# main.net
KiCad netlist of a schematic drawn in Altium Designer
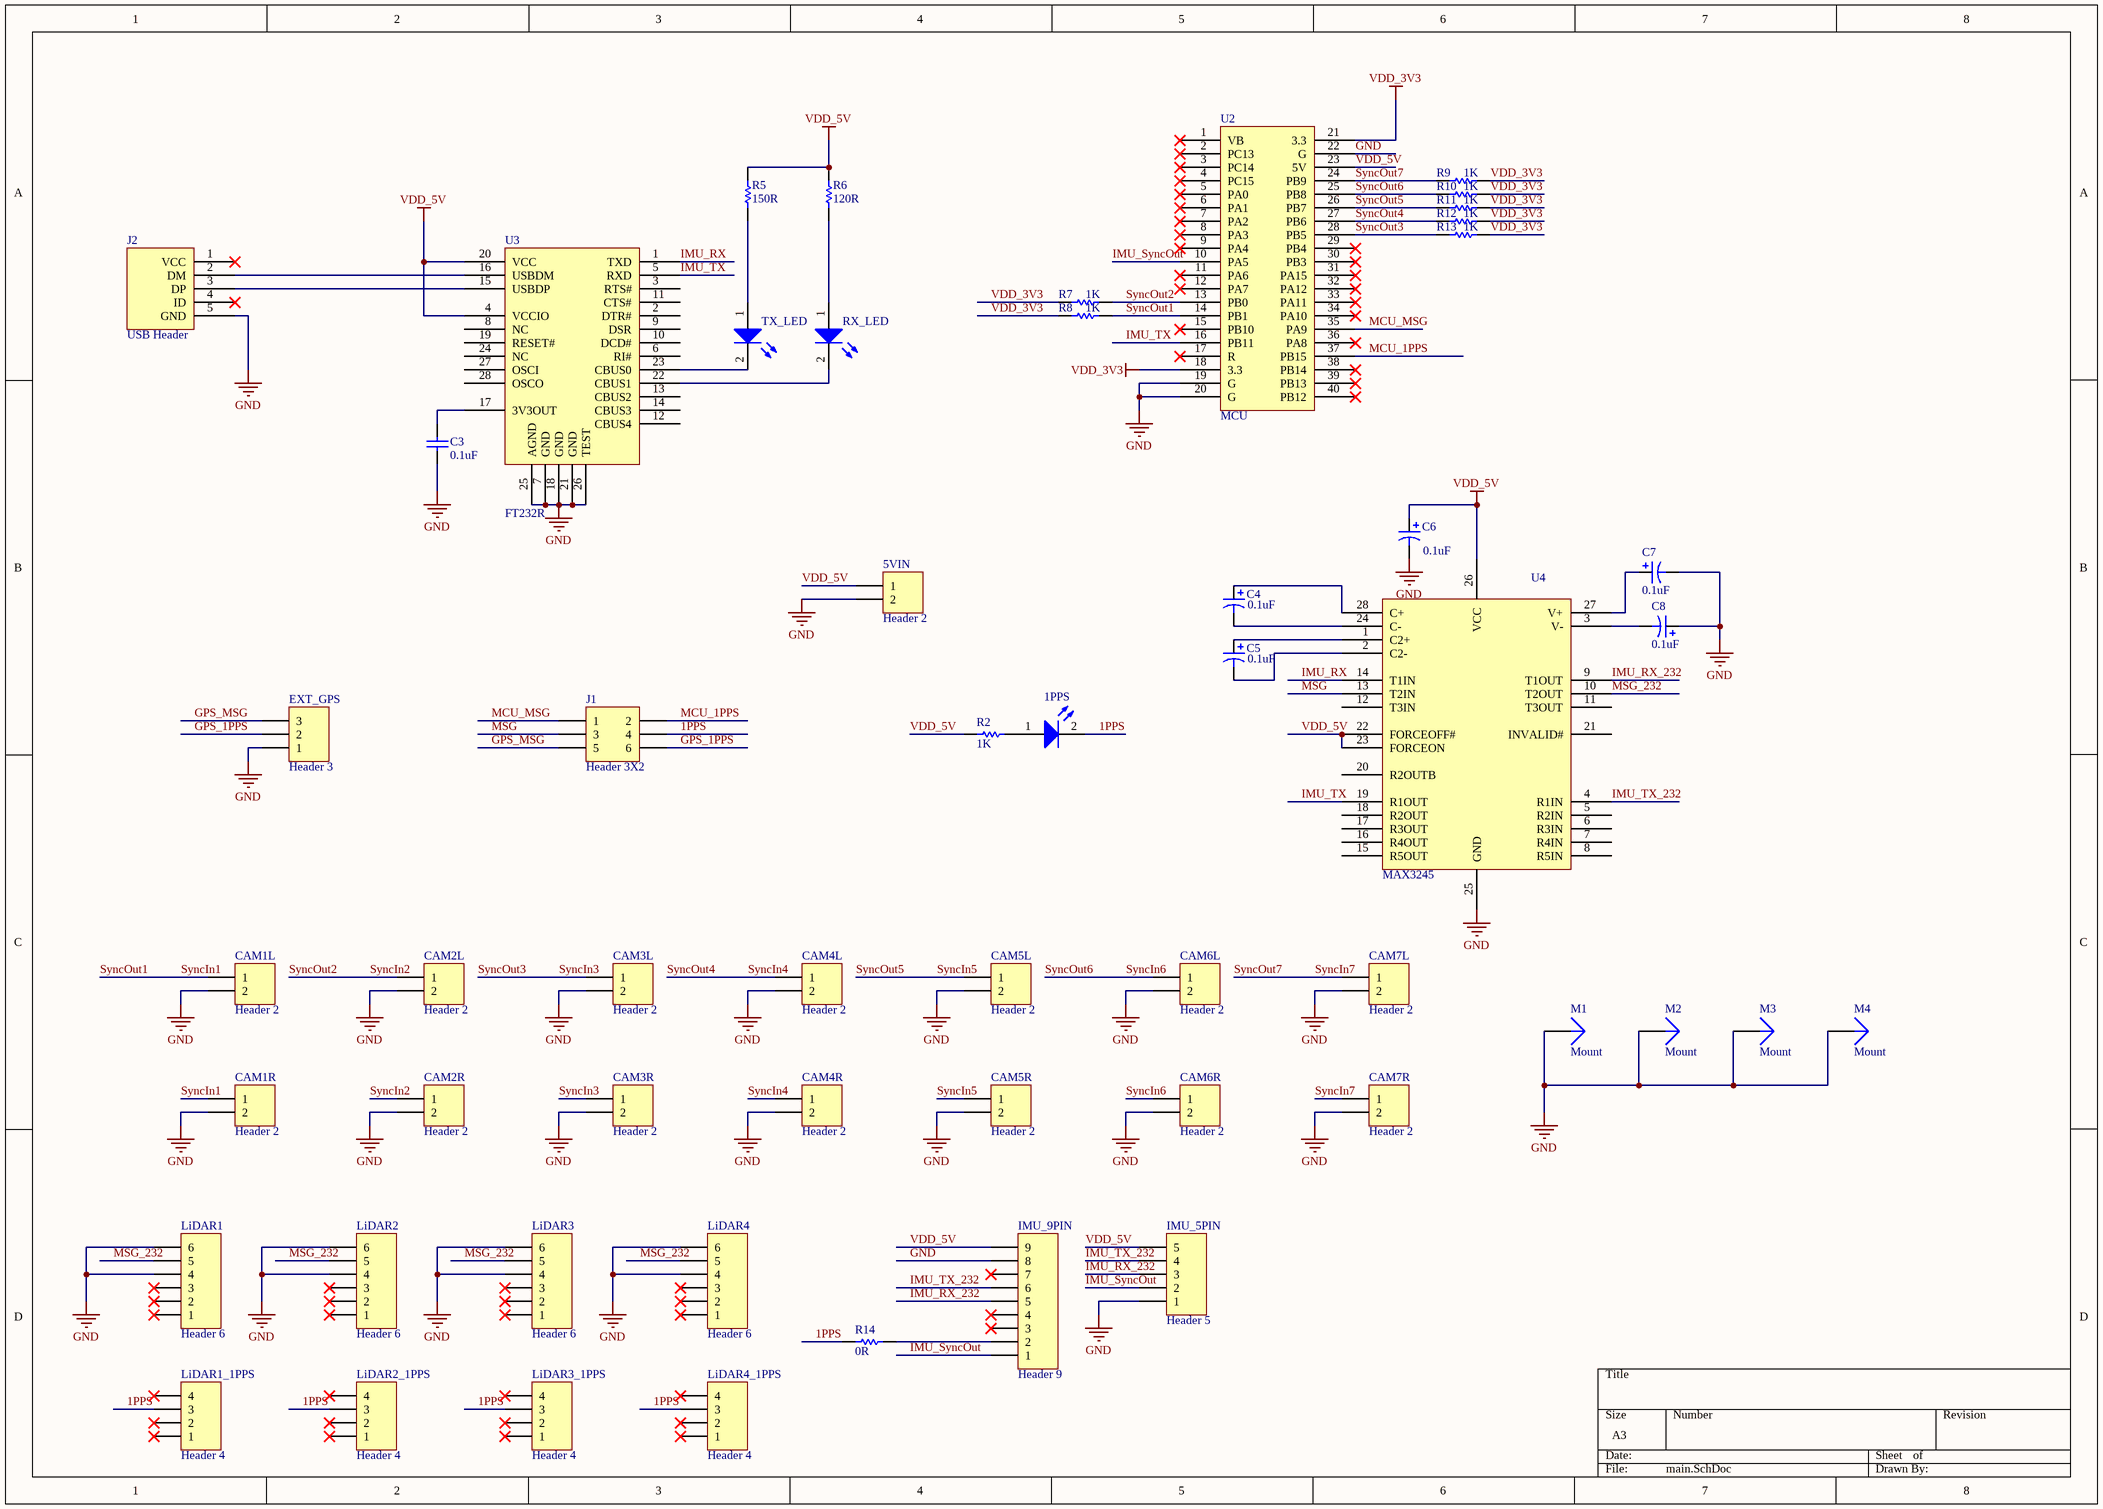
[diagram p0: main.SchDoc]

(export (version "E")
  (design (tool "Eeschema 10.0.6"))
  (components
    (comp (ref "1PPS")
      (value "1PPS LED")
      (footprint "0805D")
      (description "BLUE")
      (fields
        (field (name "MANUFACTURER") "Generic Components")
        (field (name "PUBLISHER") "Altium Hobart Technology Centre")
      )
      (libsource (lib "Miscellaneous Devices") (part "LED2"))
    )
    (comp (ref "5VIN")
      (value "Header 2")
      (footprint "HDR1X2")
      (description "Header, 2-Pin")
      (fields (field (name "PUBLISHER") "Altium Limited"))
      (libsource (lib "Miscellaneous Connectors") (part "Header 2"))
    )
    (comp (ref "C3")
      (value "0.1uF")
      (footprint "0805C")
      (description "Capacitor")
      (fields (field (name "PUBLISHER") "Altium Limited"))
      (libsource (lib "Miscellaneous Devices") (part "Cap"))
    )
    (comp (ref "C4")
      (value "0.1uF")
      (footprint "C1206")
      (description "Polarized Capacitor (Surface Mount)")
      (fields (field (name "PUBLISHER") "Altium Limited"))
      (libsource (lib "Miscellaneous Devices") (part "Cap Pol3"))
    )
    (comp (ref "C5")
      (value "0.1uF")
      (footprint "C1206")
      (description "Polarized Capacitor (Surface Mount)")
      (fields (field (name "PUBLISHER") "Altium Limited"))
      (libsource (lib "Miscellaneous Devices") (part "Cap Pol3"))
    )
    (comp (ref "C6")
      (value "0.1uF")
      (footprint "C1206")
      (description "Polarized Capacitor (Surface Mount)")
      (fields (field (name "PUBLISHER") "Altium Limited"))
      (libsource (lib "Miscellaneous Devices") (part "Cap Pol3"))
    )
    (comp (ref "C7")
      (value "0.1uF")
      (footprint "C1206")
      (description "Polarized Capacitor (Surface Mount)")
      (fields (field (name "PUBLISHER") "Altium Limited"))
      (libsource (lib "Miscellaneous Devices") (part "Cap Pol3"))
    )
    (comp (ref "C8")
      (value "0.1uF")
      (footprint "C1206")
      (description "Polarized Capacitor (Surface Mount)")
      (fields (field (name "PUBLISHER") "Altium Limited"))
      (libsource (lib "Miscellaneous Devices") (part "Cap Pol3"))
    )
    (comp (ref "CAM1L")
      (value "Header 2")
      (footprint "1.25mmP2")
      (description "Header, 2-Pin")
      (fields (field (name "PUBLISHER") "Altium Limited"))
      (libsource (lib "Miscellaneous Connectors") (part "Header 2"))
    )
    (comp (ref "CAM1R")
      (value "Header 2")
      (footprint "1.25mmP2")
      (description "Header, 2-Pin")
      (fields (field (name "PUBLISHER") "Altium Limited"))
      (libsource (lib "Miscellaneous Connectors") (part "Header 2"))
    )
    (comp (ref "CAM2L")
      (value "Header 2")
      (footprint "1.25mmP2")
      (description "Header, 2-Pin")
      (fields (field (name "PUBLISHER") "Altium Limited"))
      (libsource (lib "Miscellaneous Connectors") (part "Header 2"))
    )
    (comp (ref "CAM2R")
      (value "Header 2")
      (footprint "1.25mmP2")
      (description "Header, 2-Pin")
      (fields (field (name "PUBLISHER") "Altium Limited"))
      (libsource (lib "Miscellaneous Connectors") (part "Header 2"))
    )
    (comp (ref "CAM3L")
      (value "Header 2")
      (footprint "1.25mmP2")
      (description "Header, 2-Pin")
      (fields (field (name "PUBLISHER") "Altium Limited"))
      (libsource (lib "Miscellaneous Connectors") (part "Header 2"))
    )
    (comp (ref "CAM3R")
      (value "Header 2")
      (footprint "1.25mmP2")
      (description "Header, 2-Pin")
      (fields (field (name "PUBLISHER") "Altium Limited"))
      (libsource (lib "Miscellaneous Connectors") (part "Header 2"))
    )
    (comp (ref "CAM4L")
      (value "Header 2")
      (footprint "1.25mmP2")
      (description "Header, 2-Pin")
      (fields (field (name "PUBLISHER") "Altium Limited"))
      (libsource (lib "Miscellaneous Connectors") (part "Header 2"))
    )
    (comp (ref "CAM4R")
      (value "Header 2")
      (footprint "1.25mmP2")
      (description "Header, 2-Pin")
      (fields (field (name "PUBLISHER") "Altium Limited"))
      (libsource (lib "Miscellaneous Connectors") (part "Header 2"))
    )
    (comp (ref "CAM5L")
      (value "Header 2")
      (footprint "1.25mmP2")
      (description "Header, 2-Pin")
      (fields (field (name "PUBLISHER") "Altium Limited"))
      (libsource (lib "Miscellaneous Connectors") (part "Header 2"))
    )
    (comp (ref "CAM5R")
      (value "Header 2")
      (footprint "1.25mmP2")
      (description "Header, 2-Pin")
      (fields (field (name "PUBLISHER") "Altium Limited"))
      (libsource (lib "Miscellaneous Connectors") (part "Header 2"))
    )
    (comp (ref "CAM6L")
      (value "Header 2")
      (footprint "1.25mmP2")
      (description "Header, 2-Pin")
      (fields (field (name "PUBLISHER") "Altium Limited"))
      (libsource (lib "Miscellaneous Connectors") (part "Header 2"))
    )
    (comp (ref "CAM6R")
      (value "Header 2")
      (footprint "1.25mmP2")
      (description "Header, 2-Pin")
      (fields (field (name "PUBLISHER") "Altium Limited"))
      (libsource (lib "Miscellaneous Connectors") (part "Header 2"))
    )
    (comp (ref "CAM7L")
      (value "Header 2")
      (footprint "1.25mmP2")
      (description "Header, 2-Pin")
      (fields (field (name "PUBLISHER") "Altium Limited"))
      (libsource (lib "Miscellaneous Connectors") (part "Header 2"))
    )
    (comp (ref "CAM7R")
      (value "Header 2")
      (footprint "1.25mmP2")
      (description "Header, 2-Pin")
      (fields (field (name "PUBLISHER") "Altium Limited"))
      (libsource (lib "Miscellaneous Connectors") (part "Header 2"))
    )
    (comp (ref "EXT_GPS")
      (value "Header 3")
      (footprint "1.25mmP3")
      (description "Header, 3-Pin")
      (fields (field (name "PUBLISHER") "Altium Limited"))
      (libsource (lib "Miscellaneous Connectors") (part "Header 3"))
    )
    (comp (ref "IMU_5PIN")
      (value "Header 5")
      (footprint "1.25mmP5")
      (description "Header, 5-Pin")
      (fields (field (name "PUBLISHER") "Altium Limited"))
      (libsource (lib "Miscellaneous Connectors") (part "Header 5"))
    )
    (comp (ref "IMU_9PIN")
      (value "Header 9")
      (footprint "1.25mmP9")
      (description "Header, 9-Pin")
      (fields (field (name "PUBLISHER") "Altium Limited"))
      (libsource (lib "Miscellaneous Connectors") (part "Header 9"))
    )
    (comp (ref "J1")
      (value "Header 3X2")
      (footprint "HDR2X3")
      (description "Header, 3-Pin, Dual row")
      (fields (field (name "PUBLISHER") "Altium Limited"))
      (libsource (lib "Miscellaneous Connectors") (part "Header 3X2"))
    )
    (comp (ref "J2") (value "USB Header") (footprint "USB2.5-2H4D") (libsource (lib "USB") (part "USB")))
    (comp (ref "LiDAR1")
      (value "Header 6")
      (footprint "1.25mmP6")
      (description "Header, 6-Pin")
      (fields (field (name "PUBLISHER") "Altium Limited"))
      (libsource (lib "Miscellaneous Connectors") (part "Header 6"))
    )
    (comp (ref "LiDAR1_1PPS")
      (value "Header 4")
      (footprint "1.25mmP4")
      (description "Header, 4-Pin")
      (fields (field (name "PUBLISHER") "Altium Limited"))
      (libsource (lib "Miscellaneous Connectors") (part "Header 4"))
    )
    (comp (ref "LiDAR2")
      (value "Header 6")
      (footprint "1.25mmP6")
      (description "Header, 6-Pin")
      (fields (field (name "PUBLISHER") "Altium Limited"))
      (libsource (lib "Miscellaneous Connectors") (part "Header 6"))
    )
    (comp (ref "LiDAR2_1PPS")
      (value "Header 4")
      (footprint "1.25mmP4")
      (description "Header, 4-Pin")
      (fields (field (name "PUBLISHER") "Altium Limited"))
      (libsource (lib "Miscellaneous Connectors") (part "Header 4"))
    )
    (comp (ref "LiDAR3")
      (value "Header 6")
      (footprint "1.25mmP6")
      (description "Header, 6-Pin")
      (fields (field (name "PUBLISHER") "Altium Limited"))
      (libsource (lib "Miscellaneous Connectors") (part "Header 6"))
    )
    (comp (ref "LiDAR3_1PPS")
      (value "Header 4")
      (footprint "1.25mmP4")
      (description "Header, 4-Pin")
      (fields (field (name "PUBLISHER") "Altium Limited"))
      (libsource (lib "Miscellaneous Connectors") (part "Header 4"))
    )
    (comp (ref "LiDAR4")
      (value "Header 6")
      (footprint "1.25mmP6")
      (description "Header, 6-Pin")
      (fields (field (name "PUBLISHER") "Altium Limited"))
      (libsource (lib "Miscellaneous Connectors") (part "Header 6"))
    )
    (comp (ref "LiDAR4_1PPS")
      (value "Header 4")
      (footprint "1.25mmP4")
      (description "Header, 4-Pin")
      (fields (field (name "PUBLISHER") "Altium Limited"))
      (libsource (lib "Miscellaneous Connectors") (part "Header 4"))
    )
    (comp (ref "M1")
      (value "Mount")
      (footprint "安装孔-3.5-5")
      (description "Plug")
      (fields (field (name "PUBLISHER") "Altium Limited"))
      (libsource (lib "Miscellaneous Connectors") (part "Plug"))
    )
    (comp (ref "M2")
      (value "Mount")
      (footprint "安装孔-3.5-5")
      (description "Plug")
      (fields (field (name "PUBLISHER") "Altium Limited"))
      (libsource (lib "Miscellaneous Connectors") (part "Plug"))
    )
    (comp (ref "M3")
      (value "Mount")
      (footprint "安装孔-3.5-5")
      (description "Plug")
      (fields (field (name "PUBLISHER") "Altium Limited"))
      (libsource (lib "Miscellaneous Connectors") (part "Plug"))
    )
    (comp (ref "M4")
      (value "Mount")
      (footprint "安装孔-3.5-5")
      (description "Plug")
      (fields (field (name "PUBLISHER") "Altium Limited"))
      (libsource (lib "Miscellaneous Connectors") (part "Plug"))
    )
    (comp (ref "R2")
      (value "1K")
      (footprint "0805R")
      (description "Resistor")
      (fields
        (field (name "MANUFACTURER") "Generic Components")
        (field (name "PUBLISHER") "Altium Hobart Technology Centre")
      )
      (libsource (lib "HAIBAO_MEGAV1.0_1") (part "Res1"))
    )
    (comp (ref "R5")
      (value "150R")
      (footprint "0805R")
      (description "Resistor")
      (fields
        (field (name "MANUFACTURER") "Generic Components")
        (field (name "PUBLISHER") "Altium Hobart Technology Centre")
      )
      (libsource (lib "HAIBAO_MEGAV1.0_1") (part "Res1"))
    )
    (comp (ref "R6")
      (value "120R")
      (footprint "0805R")
      (description "Resistor")
      (fields
        (field (name "MANUFACTURER") "Generic Components")
        (field (name "PUBLISHER") "Altium Hobart Technology Centre")
      )
      (libsource (lib "HAIBAO_MEGAV1.0_1") (part "Res1"))
    )
    (comp (ref "R7")
      (value "1K")
      (footprint "0805R")
      (description "Resistor")
      (fields
        (field (name "MANUFACTURER") "Generic Components")
        (field (name "PUBLISHER") "Altium Hobart Technology Centre")
      )
      (libsource (lib "HAIBAO_MEGAV1.0_1") (part "Res1"))
    )
    (comp (ref "R8")
      (value "1K")
      (footprint "0805R")
      (description "Resistor")
      (fields
        (field (name "MANUFACTURER") "Generic Components")
        (field (name "PUBLISHER") "Altium Hobart Technology Centre")
      )
      (libsource (lib "HAIBAO_MEGAV1.0_1") (part "Res1"))
    )
    (comp (ref "R9")
      (value "1K")
      (footprint "0805R")
      (description "Resistor")
      (fields
        (field (name "MANUFACTURER") "Generic Components")
        (field (name "PUBLISHER") "Altium Hobart Technology Centre")
      )
      (libsource (lib "HAIBAO_MEGAV1.0_1") (part "Res1"))
    )
    (comp (ref "R10")
      (value "1K")
      (footprint "0805R")
      (description "Resistor")
      (fields
        (field (name "MANUFACTURER") "Generic Components")
        (field (name "PUBLISHER") "Altium Hobart Technology Centre")
      )
      (libsource (lib "HAIBAO_MEGAV1.0_1") (part "Res1"))
    )
    (comp (ref "R11")
      (value "1K")
      (footprint "0805R")
      (description "Resistor")
      (fields
        (field (name "MANUFACTURER") "Generic Components")
        (field (name "PUBLISHER") "Altium Hobart Technology Centre")
      )
      (libsource (lib "HAIBAO_MEGAV1.0_1") (part "Res1"))
    )
    (comp (ref "R12")
      (value "1K")
      (footprint "0805R")
      (description "Resistor")
      (fields
        (field (name "MANUFACTURER") "Generic Components")
        (field (name "PUBLISHER") "Altium Hobart Technology Centre")
      )
      (libsource (lib "HAIBAO_MEGAV1.0_1") (part "Res1"))
    )
    (comp (ref "R13")
      (value "1K")
      (footprint "0805R")
      (description "Resistor")
      (fields
        (field (name "MANUFACTURER") "Generic Components")
        (field (name "PUBLISHER") "Altium Hobart Technology Centre")
      )
      (libsource (lib "HAIBAO_MEGAV1.0_1") (part "Res1"))
    )
    (comp (ref "R14")
      (value "0R")
      (footprint "0805R")
      (description "Resistor")
      (fields
        (field (name "MANUFACTURER") "Generic Components")
        (field (name "PUBLISHER") "Altium Hobart Technology Centre")
      )
      (libsource (lib "HAIBAO_MEGAV1.0_1") (part "Res1"))
    )
    (comp (ref "RX_LED")
      (value "USB RX LED")
      (footprint "0805D")
      (description "GREEN")
      (fields
        (field (name "MANUFACTURER") "Generic Components")
        (field (name "PUBLISHER") "Altium Hobart Technology Centre")
      )
      (libsource (lib "Miscellaneous Devices") (part "LED2"))
    )
    (comp (ref "TX_LED")
      (value "USB TX LED")
      (footprint "0805D")
      (description "YELLOW")
      (fields
        (field (name "MANUFACTURER") "Generic Components")
        (field (name "PUBLISHER") "Altium Hobart Technology Centre")
      )
      (libsource (lib "Miscellaneous Devices") (part "LED2"))
    )
    (comp (ref "U2") (value "MCU") (footprint "STM32Board") (libsource (lib "MCU") (part "MCU")))
    (comp (ref "U3") (value "FT232R") (footprint "SSOP-28") (libsource (lib "FT232R") (part "FT232R")))
    (comp (ref "U4") (value "MAX3245") (footprint "SSOP-28") (libsource (lib "MAX3245") (part "MAX3245")))
  )
  (nets
    (net (code "1") (name "/1PPS") (class "Default")
      (node (ref "1PPS") (pin "2") (pinfunction "K_2") (pintype "passive"))
      (node (ref "J1") (pin "4") (pinfunction "4_4") (pintype "passive"))
      (node (ref "LiDAR1_1PPS") (pin "3") (pinfunction "3_3") (pintype "passive"))
      (node (ref "LiDAR2_1PPS") (pin "3") (pinfunction "3_3") (pintype "passive"))
      (node (ref "LiDAR3_1PPS") (pin "3") (pinfunction "3_3") (pintype "passive"))
      (node (ref "LiDAR4_1PPS") (pin "3") (pinfunction "3_3") (pintype "passive"))
      (node (ref "R14") (pin "1") (pinfunction "1_1") (pintype "passive"))
    )
    (net (code "2") (name "/GPS_1PPS") (class "Default")
      (node (ref "EXT_GPS") (pin "2") (pinfunction "2_2") (pintype "passive"))
      (node (ref "J1") (pin "6") (pinfunction "6_6") (pintype "passive"))
    )
    (net (code "3") (name "/GPS_MSG") (class "Default")
      (node (ref "EXT_GPS") (pin "3") (pinfunction "3_3") (pintype "passive"))
      (node (ref "J1") (pin "5") (pinfunction "5_5") (pintype "passive"))
    )
    (net (code "4") (name "/IMU_RX") (class "Default")
      (node (ref "U3") (pin "1") (pinfunction "TXD_1") (pintype "passive"))
      (node (ref "U4") (pin "14") (pinfunction "T1IN_14") (pintype "passive"))
    )
    (net (code "5") (name "/IMU_RX_232") (class "Default")
      (node (ref "IMU_5PIN") (pin "3") (pinfunction "3_3") (pintype "passive"))
      (node (ref "IMU_9PIN") (pin "5") (pinfunction "5_5") (pintype "passive"))
      (node (ref "U4") (pin "9") (pinfunction "T1OUT_9") (pintype "passive"))
    )
    (net (code "6") (name "/IMU_SyncOut") (class "Default")
      (node (ref "IMU_5PIN") (pin "2") (pinfunction "2_2") (pintype "passive"))
      (node (ref "IMU_9PIN") (pin "1") (pinfunction "1_1") (pintype "passive"))
      (node (ref "U2") (pin "10") (pinfunction "PA5_10") (pintype "passive"))
    )
    (net (code "7") (name "/IMU_TX") (class "Default")
      (node (ref "U2") (pin "16") (pinfunction "PB11_16") (pintype "passive"))
      (node (ref "U3") (pin "5") (pinfunction "RXD_5") (pintype "passive"))
      (node (ref "U4") (pin "19") (pinfunction "R1OUT_19") (pintype "passive"))
    )
    (net (code "8") (name "/IMU_TX_232") (class "Default")
      (node (ref "IMU_5PIN") (pin "4") (pinfunction "4_4") (pintype "passive"))
      (node (ref "IMU_9PIN") (pin "6") (pinfunction "6_6") (pintype "passive"))
      (node (ref "U4") (pin "4") (pinfunction "R1IN_4") (pintype "passive"))
    )
    (net (code "9") (name "/MCU_1PPS") (class "Default")
      (node (ref "J1") (pin "2") (pinfunction "2_2") (pintype "passive"))
      (node (ref "U2") (pin "37") (pinfunction "PB15_37") (pintype "passive"))
    )
    (net (code "10") (name "/MCU_MSG") (class "Default")
      (node (ref "J1") (pin "1") (pinfunction "1_1") (pintype "passive"))
      (node (ref "U2") (pin "35") (pinfunction "PA9_35") (pintype "passive"))
    )
    (net (code "11") (name "/MSG") (class "Default")
      (node (ref "J1") (pin "3") (pinfunction "3_3") (pintype "passive"))
      (node (ref "U4") (pin "13") (pinfunction "T2IN_13") (pintype "passive"))
    )
    (net (code "12") (name "/MSG_232") (class "Default")
      (node (ref "LiDAR1") (pin "5") (pinfunction "5_5") (pintype "passive"))
      (node (ref "LiDAR2") (pin "5") (pinfunction "5_5") (pintype "passive"))
      (node (ref "LiDAR3") (pin "5") (pinfunction "5_5") (pintype "passive"))
      (node (ref "LiDAR4") (pin "5") (pinfunction "5_5") (pintype "passive"))
      (node (ref "U4") (pin "10") (pinfunction "T2OUT_10") (pintype "passive"))
    )
    (net (code "13") (name "/SyncIn1") (class "Default")
      (node (ref "CAM1L") (pin "1") (pinfunction "1_1") (pintype "passive"))
      (node (ref "CAM1R") (pin "1") (pinfunction "1_1") (pintype "passive"))
      (node (ref "R8") (pin "1") (pinfunction "1_1") (pintype "passive"))
      (node (ref "U2") (pin "14") (pinfunction "PB1_14") (pintype "passive"))
    )
    (net (code "14") (name "/SyncIn2") (class "Default")
      (node (ref "CAM2L") (pin "1") (pinfunction "1_1") (pintype "passive"))
      (node (ref "CAM2R") (pin "1") (pinfunction "1_1") (pintype "passive"))
      (node (ref "R7") (pin "1") (pinfunction "1_1") (pintype "passive"))
      (node (ref "U2") (pin "13") (pinfunction "PB0_13") (pintype "passive"))
    )
    (net (code "15") (name "/SyncIn3") (class "Default")
      (node (ref "CAM3L") (pin "1") (pinfunction "1_1") (pintype "passive"))
      (node (ref "CAM3R") (pin "1") (pinfunction "1_1") (pintype "passive"))
      (node (ref "R13") (pin "2") (pinfunction "2_2") (pintype "passive"))
      (node (ref "U2") (pin "28") (pinfunction "PB5_28") (pintype "passive"))
    )
    (net (code "16") (name "/SyncIn4") (class "Default")
      (node (ref "CAM4L") (pin "1") (pinfunction "1_1") (pintype "passive"))
      (node (ref "CAM4R") (pin "1") (pinfunction "1_1") (pintype "passive"))
      (node (ref "R12") (pin "2") (pinfunction "2_2") (pintype "passive"))
      (node (ref "U2") (pin "27") (pinfunction "PB6_27") (pintype "passive"))
    )
    (net (code "17") (name "/SyncIn5") (class "Default")
      (node (ref "CAM5L") (pin "1") (pinfunction "1_1") (pintype "passive"))
      (node (ref "CAM5R") (pin "1") (pinfunction "1_1") (pintype "passive"))
      (node (ref "R11") (pin "2") (pinfunction "2_2") (pintype "passive"))
      (node (ref "U2") (pin "26") (pinfunction "PB7_26") (pintype "passive"))
    )
    (net (code "18") (name "/SyncIn6") (class "Default")
      (node (ref "CAM6L") (pin "1") (pinfunction "1_1") (pintype "passive"))
      (node (ref "CAM6R") (pin "1") (pinfunction "1_1") (pintype "passive"))
      (node (ref "R10") (pin "2") (pinfunction "2_2") (pintype "passive"))
      (node (ref "U2") (pin "25") (pinfunction "PB8_25") (pintype "passive"))
    )
    (net (code "19") (name "/SyncIn7") (class "Default")
      (node (ref "CAM7L") (pin "1") (pinfunction "1_1") (pintype "passive"))
      (node (ref "CAM7R") (pin "1") (pinfunction "1_1") (pintype "passive"))
      (node (ref "R9") (pin "2") (pinfunction "2_2") (pintype "passive"))
      (node (ref "U2") (pin "24") (pinfunction "PB9_24") (pintype "passive"))
    )
    (net (code "20") (name "GND") (class "Default")
      (node (ref "5VIN") (pin "2") (pinfunction "2_2") (pintype "passive"))
      (node (ref "C3") (pin "1") (pinfunction "1_1") (pintype "passive"))
      (node (ref "C6") (pin "2") (pinfunction "2_2") (pintype "passive"))
      (node (ref "C7") (pin "2") (pinfunction "2_2") (pintype "passive"))
      (node (ref "C8") (pin "1") (pinfunction "1_1") (pintype "passive"))
      (node (ref "CAM1L") (pin "2") (pinfunction "2_2") (pintype "passive"))
      (node (ref "CAM1R") (pin "2") (pinfunction "2_2") (pintype "passive"))
      (node (ref "CAM2L") (pin "2") (pinfunction "2_2") (pintype "passive"))
      (node (ref "CAM2R") (pin "2") (pinfunction "2_2") (pintype "passive"))
      (node (ref "CAM3L") (pin "2") (pinfunction "2_2") (pintype "passive"))
      (node (ref "CAM3R") (pin "2") (pinfunction "2_2") (pintype "passive"))
      (node (ref "CAM4L") (pin "2") (pinfunction "2_2") (pintype "passive"))
      (node (ref "CAM4R") (pin "2") (pinfunction "2_2") (pintype "passive"))
      (node (ref "CAM5L") (pin "2") (pinfunction "2_2") (pintype "passive"))
      (node (ref "CAM5R") (pin "2") (pinfunction "2_2") (pintype "passive"))
      (node (ref "CAM6L") (pin "2") (pinfunction "2_2") (pintype "passive"))
      (node (ref "CAM6R") (pin "2") (pinfunction "2_2") (pintype "passive"))
      (node (ref "CAM7L") (pin "2") (pinfunction "2_2") (pintype "passive"))
      (node (ref "CAM7R") (pin "2") (pinfunction "2_2") (pintype "passive"))
      (node (ref "EXT_GPS") (pin "1") (pinfunction "1_1") (pintype "passive"))
      (node (ref "IMU_5PIN") (pin "1") (pinfunction "1_1") (pintype "passive"))
      (node (ref "IMU_9PIN") (pin "8") (pinfunction "8_8") (pintype "passive"))
      (node (ref "J2") (pin "5") (pinfunction "GND_5") (pintype "passive"))
      (node (ref "LiDAR1") (pin "4") (pinfunction "4_4") (pintype "passive"))
      (node (ref "LiDAR1") (pin "6") (pinfunction "6_6") (pintype "passive"))
      (node (ref "LiDAR2") (pin "4") (pinfunction "4_4") (pintype "passive"))
      (node (ref "LiDAR2") (pin "6") (pinfunction "6_6") (pintype "passive"))
      (node (ref "LiDAR3") (pin "4") (pinfunction "4_4") (pintype "passive"))
      (node (ref "LiDAR3") (pin "6") (pinfunction "6_6") (pintype "passive"))
      (node (ref "LiDAR4") (pin "4") (pinfunction "4_4") (pintype "passive"))
      (node (ref "LiDAR4") (pin "6") (pinfunction "6_6") (pintype "passive"))
      (node (ref "M1") (pin "1") (pinfunction "1_1") (pintype "passive"))
      (node (ref "M2") (pin "1") (pinfunction "1_1") (pintype "passive"))
      (node (ref "M3") (pin "1") (pinfunction "1_1") (pintype "passive"))
      (node (ref "M4") (pin "1") (pinfunction "1_1") (pintype "passive"))
      (node (ref "U2") (pin "19") (pinfunction "G_19") (pintype "passive"))
      (node (ref "U2") (pin "20") (pinfunction "G_20") (pintype "passive"))
      (node (ref "U2") (pin "22") (pinfunction "G_22") (pintype "passive"))
      (node (ref "U3") (pin "18") (pinfunction "GND_18") (pintype "passive"))
      (node (ref "U3") (pin "21") (pinfunction "GND_21") (pintype "passive"))
      (node (ref "U3") (pin "25") (pinfunction "AGND_25") (pintype "passive"))
      (node (ref "U3") (pin "26") (pinfunction "TEST_26") (pintype "passive"))
      (node (ref "U3") (pin "7") (pinfunction "GND_7") (pintype "passive"))
      (node (ref "U4") (pin "25") (pinfunction "GND_25") (pintype "passive"))
    )
    (net (code "21") (name "Net-(1PPS-A)") (class "Default")
      (node (ref "1PPS") (pin "1") (pinfunction "A_1") (pintype "passive"))
      (node (ref "R2") (pin "1") (pinfunction "1_1") (pintype "passive"))
    )
    (net (code "22") (name "Net-(IMU_9PIN-Pad2)") (class "Default")
      (node (ref "IMU_9PIN") (pin "2") (pinfunction "2_2") (pintype "passive"))
      (node (ref "R14") (pin "2") (pinfunction "2_2") (pintype "passive"))
    )
    (net (code "23") (name "Net-(J2-DM)") (class "Default")
      (node (ref "J2") (pin "2") (pinfunction "DM_2") (pintype "passive"))
      (node (ref "U3") (pin "16") (pinfunction "USBDM_16") (pintype "passive"))
    )
    (net (code "24") (name "Net-(J2-DP)") (class "Default")
      (node (ref "J2") (pin "3") (pinfunction "DP_3") (pintype "passive"))
      (node (ref "U3") (pin "15") (pinfunction "USBDP_15") (pintype "passive"))
    )
    (net (code "25") (name "Net-(RX_LED-A)") (class "Default")
      (node (ref "R6") (pin "2") (pinfunction "2_2") (pintype "passive"))
      (node (ref "RX_LED") (pin "1") (pinfunction "A_1") (pintype "passive"))
    )
    (net (code "26") (name "Net-(RX_LED-K)") (class "Default")
      (node (ref "RX_LED") (pin "2") (pinfunction "K_2") (pintype "passive"))
      (node (ref "U3") (pin "22") (pinfunction "CBUS1_22") (pintype "passive"))
    )
    (net (code "27") (name "Net-(TX_LED-A)") (class "Default")
      (node (ref "R5") (pin "2") (pinfunction "2_2") (pintype "passive"))
      (node (ref "TX_LED") (pin "1") (pinfunction "A_1") (pintype "passive"))
    )
    (net (code "28") (name "Net-(TX_LED-K)") (class "Default")
      (node (ref "TX_LED") (pin "2") (pinfunction "K_2") (pintype "passive"))
      (node (ref "U3") (pin "23") (pinfunction "CBUS0_23") (pintype "passive"))
    )
    (net (code "29") (name "Net-(U3-3V3OUT)") (class "Default")
      (node (ref "C3") (pin "2") (pinfunction "2_2") (pintype "passive"))
      (node (ref "U3") (pin "17") (pinfunction "3V3OUT_17") (pintype "passive"))
    )
    (net (code "30") (name "Net-(U4-C+)") (class "Default")
      (node (ref "C4") (pin "1") (pinfunction "1_1") (pintype "passive"))
      (node (ref "U4") (pin "28") (pinfunction "C+_28") (pintype "passive"))
    )
    (net (code "31") (name "Net-(U4-C-)") (class "Default")
      (node (ref "C4") (pin "2") (pinfunction "2_2") (pintype "passive"))
      (node (ref "U4") (pin "24") (pinfunction "C-_24") (pintype "passive"))
    )
    (net (code "32") (name "Net-(U4-C2+)") (class "Default")
      (node (ref "C5") (pin "1") (pinfunction "1_1") (pintype "passive"))
      (node (ref "U4") (pin "1") (pinfunction "C2+_1") (pintype "passive"))
    )
    (net (code "33") (name "Net-(U4-C2-)") (class "Default")
      (node (ref "C5") (pin "2") (pinfunction "2_2") (pintype "passive"))
      (node (ref "U4") (pin "2") (pinfunction "C2-_2") (pintype "passive"))
    )
    (net (code "34") (name "Net-(U4-V+)") (class "Default")
      (node (ref "C7") (pin "1") (pinfunction "1_1") (pintype "passive"))
      (node (ref "U4") (pin "27") (pinfunction "V+_27") (pintype "passive"))
    )
    (net (code "35") (name "Net-(U4-V-)") (class "Default")
      (node (ref "C8") (pin "2") (pinfunction "2_2") (pintype "passive"))
      (node (ref "U4") (pin "3") (pinfunction "V-_3") (pintype "passive"))
    )
    (net (code "36") (name "VDD_3V3") (class "Default")
      (node (ref "R10") (pin "1") (pinfunction "1_1") (pintype "passive"))
      (node (ref "R11") (pin "1") (pinfunction "1_1") (pintype "passive"))
      (node (ref "R12") (pin "1") (pinfunction "1_1") (pintype "passive"))
      (node (ref "R13") (pin "1") (pinfunction "1_1") (pintype "passive"))
      (node (ref "R7") (pin "2") (pinfunction "2_2") (pintype "passive"))
      (node (ref "R8") (pin "2") (pinfunction "2_2") (pintype "passive"))
      (node (ref "R9") (pin "1") (pinfunction "1_1") (pintype "passive"))
      (node (ref "U2") (pin "18") (pinfunction "3.3_18") (pintype "passive"))
      (node (ref "U2") (pin "21") (pinfunction "3.3_21") (pintype "passive"))
    )
    (net (code "37") (name "VDD_5V") (class "Default")
      (node (ref "5VIN") (pin "1") (pinfunction "1_1") (pintype "passive"))
      (node (ref "C6") (pin "1") (pinfunction "1_1") (pintype "passive"))
      (node (ref "IMU_5PIN") (pin "5") (pinfunction "5_5") (pintype "passive"))
      (node (ref "IMU_9PIN") (pin "9") (pinfunction "9_9") (pintype "passive"))
      (node (ref "R2") (pin "2") (pinfunction "2_2") (pintype "passive"))
      (node (ref "R5") (pin "1") (pinfunction "1_1") (pintype "passive"))
      (node (ref "R6") (pin "1") (pinfunction "1_1") (pintype "passive"))
      (node (ref "U2") (pin "23") (pinfunction "5V_23") (pintype "passive"))
      (node (ref "U3") (pin "20") (pinfunction "VCC_20") (pintype "passive"))
      (node (ref "U3") (pin "4") (pinfunction "VCCIO_4") (pintype "passive"))
      (node (ref "U4") (pin "22") (pinfunction "FORCEOFF#_22") (pintype "passive"))
      (node (ref "U4") (pin "23") (pinfunction "FORCEON_23") (pintype "passive"))
      (node (ref "U4") (pin "26") (pinfunction "VCC_26") (pintype "passive"))
    )
    (net (code "38") (name "unconnected-(IMU_9PIN-Pad3)") (class "Default")
      (node (ref "IMU_9PIN") (pin "3") (pinfunction "3_3") (pintype "passive+no_connect"))
    )
    (net (code "39") (name "unconnected-(IMU_9PIN-Pad4)") (class "Default")
      (node (ref "IMU_9PIN") (pin "4") (pinfunction "4_4") (pintype "passive+no_connect"))
    )
    (net (code "40") (name "unconnected-(IMU_9PIN-Pad7)") (class "Default")
      (node (ref "IMU_9PIN") (pin "7") (pinfunction "7_7") (pintype "passive+no_connect"))
    )
    (net (code "41") (name "unconnected-(J2-ID-Pad4)") (class "Default")
      (node (ref "J2") (pin "4") (pinfunction "ID_4") (pintype "passive+no_connect"))
    )
    (net (code "42") (name "unconnected-(J2-VCC-Pad1)") (class "Default")
      (node (ref "J2") (pin "1") (pinfunction "VCC_1") (pintype "passive+no_connect"))
    )
    (net (code "43") (name "unconnected-(LiDAR1-Pad1)") (class "Default")
      (node (ref "LiDAR1") (pin "1") (pinfunction "1_1") (pintype "passive+no_connect"))
    )
    (net (code "44") (name "unconnected-(LiDAR1-Pad2)") (class "Default")
      (node (ref "LiDAR1") (pin "2") (pinfunction "2_2") (pintype "passive+no_connect"))
    )
    (net (code "45") (name "unconnected-(LiDAR1-Pad3)") (class "Default")
      (node (ref "LiDAR1") (pin "3") (pinfunction "3_3") (pintype "passive+no_connect"))
    )
    (net (code "46") (name "unconnected-(LiDAR1_1PPS-Pad1)") (class "Default")
      (node (ref "LiDAR1_1PPS") (pin "1") (pinfunction "1_1") (pintype "passive+no_connect"))
    )
    (net (code "47") (name "unconnected-(LiDAR1_1PPS-Pad2)") (class "Default")
      (node (ref "LiDAR1_1PPS") (pin "2") (pinfunction "2_2") (pintype "passive+no_connect"))
    )
    (net (code "48") (name "unconnected-(LiDAR1_1PPS-Pad4)") (class "Default")
      (node (ref "LiDAR1_1PPS") (pin "4") (pinfunction "4_4") (pintype "passive+no_connect"))
    )
    (net (code "49") (name "unconnected-(LiDAR2-Pad1)") (class "Default")
      (node (ref "LiDAR2") (pin "1") (pinfunction "1_1") (pintype "passive+no_connect"))
    )
    (net (code "50") (name "unconnected-(LiDAR2-Pad2)") (class "Default")
      (node (ref "LiDAR2") (pin "2") (pinfunction "2_2") (pintype "passive+no_connect"))
    )
    (net (code "51") (name "unconnected-(LiDAR2-Pad3)") (class "Default")
      (node (ref "LiDAR2") (pin "3") (pinfunction "3_3") (pintype "passive+no_connect"))
    )
    (net (code "52") (name "unconnected-(LiDAR2_1PPS-Pad1)") (class "Default")
      (node (ref "LiDAR2_1PPS") (pin "1") (pinfunction "1_1") (pintype "passive+no_connect"))
    )
    (net (code "53") (name "unconnected-(LiDAR2_1PPS-Pad2)") (class "Default")
      (node (ref "LiDAR2_1PPS") (pin "2") (pinfunction "2_2") (pintype "passive+no_connect"))
    )
    (net (code "54") (name "unconnected-(LiDAR2_1PPS-Pad4)") (class "Default")
      (node (ref "LiDAR2_1PPS") (pin "4") (pinfunction "4_4") (pintype "passive+no_connect"))
    )
    (net (code "55") (name "unconnected-(LiDAR3-Pad1)") (class "Default")
      (node (ref "LiDAR3") (pin "1") (pinfunction "1_1") (pintype "passive+no_connect"))
    )
    (net (code "56") (name "unconnected-(LiDAR3-Pad2)") (class "Default")
      (node (ref "LiDAR3") (pin "2") (pinfunction "2_2") (pintype "passive+no_connect"))
    )
    (net (code "57") (name "unconnected-(LiDAR3-Pad3)") (class "Default")
      (node (ref "LiDAR3") (pin "3") (pinfunction "3_3") (pintype "passive+no_connect"))
    )
    (net (code "58") (name "unconnected-(LiDAR3_1PPS-Pad1)") (class "Default")
      (node (ref "LiDAR3_1PPS") (pin "1") (pinfunction "1_1") (pintype "passive+no_connect"))
    )
    (net (code "59") (name "unconnected-(LiDAR3_1PPS-Pad2)") (class "Default")
      (node (ref "LiDAR3_1PPS") (pin "2") (pinfunction "2_2") (pintype "passive+no_connect"))
    )
    (net (code "60") (name "unconnected-(LiDAR3_1PPS-Pad4)") (class "Default")
      (node (ref "LiDAR3_1PPS") (pin "4") (pinfunction "4_4") (pintype "passive+no_connect"))
    )
    (net (code "61") (name "unconnected-(LiDAR4-Pad1)") (class "Default")
      (node (ref "LiDAR4") (pin "1") (pinfunction "1_1") (pintype "passive+no_connect"))
    )
    (net (code "62") (name "unconnected-(LiDAR4-Pad2)") (class "Default")
      (node (ref "LiDAR4") (pin "2") (pinfunction "2_2") (pintype "passive+no_connect"))
    )
    (net (code "63") (name "unconnected-(LiDAR4-Pad3)") (class "Default")
      (node (ref "LiDAR4") (pin "3") (pinfunction "3_3") (pintype "passive+no_connect"))
    )
    (net (code "64") (name "unconnected-(LiDAR4_1PPS-Pad1)") (class "Default")
      (node (ref "LiDAR4_1PPS") (pin "1") (pinfunction "1_1") (pintype "passive+no_connect"))
    )
    (net (code "65") (name "unconnected-(LiDAR4_1PPS-Pad2)") (class "Default")
      (node (ref "LiDAR4_1PPS") (pin "2") (pinfunction "2_2") (pintype "passive+no_connect"))
    )
    (net (code "66") (name "unconnected-(LiDAR4_1PPS-Pad4)") (class "Default")
      (node (ref "LiDAR4_1PPS") (pin "4") (pinfunction "4_4") (pintype "passive+no_connect"))
    )
    (net (code "67") (name "unconnected-(U2-PA0-Pad5)") (class "Default")
      (node (ref "U2") (pin "5") (pinfunction "PA0_5") (pintype "passive+no_connect"))
    )
    (net (code "68") (name "unconnected-(U2-PA1-Pad6)") (class "Default")
      (node (ref "U2") (pin "6") (pinfunction "PA1_6") (pintype "passive+no_connect"))
    )
    (net (code "69") (name "unconnected-(U2-PA2-Pad7)") (class "Default")
      (node (ref "U2") (pin "7") (pinfunction "PA2_7") (pintype "passive+no_connect"))
    )
    (net (code "70") (name "unconnected-(U2-PA3-Pad8)") (class "Default")
      (node (ref "U2") (pin "8") (pinfunction "PA3_8") (pintype "passive+no_connect"))
    )
    (net (code "71") (name "unconnected-(U2-PA4-Pad9)") (class "Default")
      (node (ref "U2") (pin "9") (pinfunction "PA4_9") (pintype "passive+no_connect"))
    )
    (net (code "72") (name "unconnected-(U2-PA6-Pad11)") (class "Default")
      (node (ref "U2") (pin "11") (pinfunction "PA6_11") (pintype "passive+no_connect"))
    )
    (net (code "73") (name "unconnected-(U2-PA7-Pad12)") (class "Default")
      (node (ref "U2") (pin "12") (pinfunction "PA7_12") (pintype "passive+no_connect"))
    )
    (net (code "74") (name "unconnected-(U2-PA8-Pad36)") (class "Default")
      (node (ref "U2") (pin "36") (pinfunction "PA8_36") (pintype "passive+no_connect"))
    )
    (net (code "75") (name "unconnected-(U2-PA10-Pad34)") (class "Default")
      (node (ref "U2") (pin "34") (pinfunction "PA10_34") (pintype "passive+no_connect"))
    )
    (net (code "76") (name "unconnected-(U2-PA11-Pad33)") (class "Default")
      (node (ref "U2") (pin "33") (pinfunction "PA11_33") (pintype "passive+no_connect"))
    )
    (net (code "77") (name "unconnected-(U2-PA12-Pad32)") (class "Default")
      (node (ref "U2") (pin "32") (pinfunction "PA12_32") (pintype "passive+no_connect"))
    )
    (net (code "78") (name "unconnected-(U2-PA15-Pad31)") (class "Default")
      (node (ref "U2") (pin "31") (pinfunction "PA15_31") (pintype "passive+no_connect"))
    )
    (net (code "79") (name "unconnected-(U2-PB3-Pad30)") (class "Default")
      (node (ref "U2") (pin "30") (pinfunction "PB3_30") (pintype "passive+no_connect"))
    )
    (net (code "80") (name "unconnected-(U2-PB4-Pad29)") (class "Default")
      (node (ref "U2") (pin "29") (pinfunction "PB4_29") (pintype "passive+no_connect"))
    )
    (net (code "81") (name "unconnected-(U2-PB10-Pad15)") (class "Default")
      (node (ref "U2") (pin "15") (pinfunction "PB10_15") (pintype "passive+no_connect"))
    )
    (net (code "82") (name "unconnected-(U2-PB12-Pad40)") (class "Default")
      (node (ref "U2") (pin "40") (pinfunction "PB12_40") (pintype "passive+no_connect"))
    )
    (net (code "83") (name "unconnected-(U2-PB13-Pad39)") (class "Default")
      (node (ref "U2") (pin "39") (pinfunction "PB13_39") (pintype "passive+no_connect"))
    )
    (net (code "84") (name "unconnected-(U2-PB14-Pad38)") (class "Default")
      (node (ref "U2") (pin "38") (pinfunction "PB14_38") (pintype "passive+no_connect"))
    )
    (net (code "85") (name "unconnected-(U2-PC13-Pad2)") (class "Default")
      (node (ref "U2") (pin "2") (pinfunction "PC13_2") (pintype "passive+no_connect"))
    )
    (net (code "86") (name "unconnected-(U2-PC14-Pad3)") (class "Default")
      (node (ref "U2") (pin "3") (pinfunction "PC14_3") (pintype "passive+no_connect"))
    )
    (net (code "87") (name "unconnected-(U2-PC15-Pad4)") (class "Default")
      (node (ref "U2") (pin "4") (pinfunction "PC15_4") (pintype "passive+no_connect"))
    )
    (net (code "88") (name "unconnected-(U2-R-Pad17)") (class "Default")
      (node (ref "U2") (pin "17") (pinfunction "R_17") (pintype "passive+no_connect"))
    )
    (net (code "89") (name "unconnected-(U2-VB-Pad1)") (class "Default")
      (node (ref "U2") (pin "1") (pinfunction "VB_1") (pintype "power_in+no_connect"))
    )
    (net (code "90") (name "unconnected-(U3-CBUS2-Pad13)") (class "Default")
      (node (ref "U3") (pin "13") (pinfunction "CBUS2_13") (pintype "passive"))
    )
    (net (code "91") (name "unconnected-(U3-CBUS3-Pad14)") (class "Default")
      (node (ref "U3") (pin "14") (pinfunction "CBUS3_14") (pintype "passive"))
    )
    (net (code "92") (name "unconnected-(U3-CBUS4-Pad12)") (class "Default")
      (node (ref "U3") (pin "12") (pinfunction "CBUS4_12") (pintype "passive"))
    )
    (net (code "93") (name "unconnected-(U3-CTS#-Pad11)") (class "Default")
      (node (ref "U3") (pin "11") (pinfunction "CTS#_11") (pintype "passive"))
    )
    (net (code "94") (name "unconnected-(U3-DCD#-Pad10)") (class "Default")
      (node (ref "U3") (pin "10") (pinfunction "DCD#_10") (pintype "passive"))
    )
    (net (code "95") (name "unconnected-(U3-DSR-Pad9)") (class "Default")
      (node (ref "U3") (pin "9") (pinfunction "DSR_9") (pintype "passive"))
    )
    (net (code "96") (name "unconnected-(U3-DTR#-Pad2)") (class "Default")
      (node (ref "U3") (pin "2") (pinfunction "DTR#_2") (pintype "passive"))
    )
    (net (code "97") (name "unconnected-(U3-NC-Pad8)") (class "Default")
      (node (ref "U3") (pin "8") (pinfunction "NC_8") (pintype "passive"))
    )
    (net (code "98") (name "unconnected-(U3-NC-Pad24)") (class "Default")
      (node (ref "U3") (pin "24") (pinfunction "NC_24") (pintype "passive"))
    )
    (net (code "99") (name "unconnected-(U3-OSCI-Pad27)") (class "Default")
      (node (ref "U3") (pin "27") (pinfunction "OSCI_27") (pintype "passive"))
    )
    (net (code "100") (name "unconnected-(U3-OSCO-Pad28)") (class "Default")
      (node (ref "U3") (pin "28") (pinfunction "OSCO_28") (pintype "passive"))
    )
    (net (code "101") (name "unconnected-(U3-RESET#-Pad19)") (class "Default")
      (node (ref "U3") (pin "19") (pinfunction "RESET#_19") (pintype "passive"))
    )
    (net (code "102") (name "unconnected-(U3-RI#-Pad6)") (class "Default")
      (node (ref "U3") (pin "6") (pinfunction "RI#_6") (pintype "passive"))
    )
    (net (code "103") (name "unconnected-(U3-RTS#-Pad3)") (class "Default")
      (node (ref "U3") (pin "3") (pinfunction "RTS#_3") (pintype "passive"))
    )
    (net (code "104") (name "unconnected-(U4-INVALID#-Pad21)") (class "Default")
      (node (ref "U4") (pin "21") (pinfunction "INVALID#_21") (pintype "passive"))
    )
    (net (code "105") (name "unconnected-(U4-R2IN-Pad5)") (class "Default")
      (node (ref "U4") (pin "5") (pinfunction "R2IN_5") (pintype "passive"))
    )
    (net (code "106") (name "unconnected-(U4-R2OUT-Pad18)") (class "Default")
      (node (ref "U4") (pin "18") (pinfunction "R2OUT_18") (pintype "passive"))
    )
    (net (code "107") (name "unconnected-(U4-R2OUTB-Pad20)") (class "Default")
      (node (ref "U4") (pin "20") (pinfunction "R2OUTB_20") (pintype "passive"))
    )
    (net (code "108") (name "unconnected-(U4-R3IN-Pad6)") (class "Default")
      (node (ref "U4") (pin "6") (pinfunction "R3IN_6") (pintype "passive"))
    )
    (net (code "109") (name "unconnected-(U4-R3OUT-Pad17)") (class "Default")
      (node (ref "U4") (pin "17") (pinfunction "R3OUT_17") (pintype "passive"))
    )
    (net (code "110") (name "unconnected-(U4-R4IN-Pad7)") (class "Default")
      (node (ref "U4") (pin "7") (pinfunction "R4IN_7") (pintype "passive"))
    )
    (net (code "111") (name "unconnected-(U4-R4OUT-Pad16)") (class "Default")
      (node (ref "U4") (pin "16") (pinfunction "R4OUT_16") (pintype "passive"))
    )
    (net (code "112") (name "unconnected-(U4-R5IN-Pad8)") (class "Default")
      (node (ref "U4") (pin "8") (pinfunction "R5IN_8") (pintype "passive"))
    )
    (net (code "113") (name "unconnected-(U4-R5OUT-Pad15)") (class "Default")
      (node (ref "U4") (pin "15") (pinfunction "R5OUT_15") (pintype "passive"))
    )
    (net (code "114") (name "unconnected-(U4-T3IN-Pad12)") (class "Default")
      (node (ref "U4") (pin "12") (pinfunction "T3IN_12") (pintype "passive"))
    )
    (net (code "115") (name "unconnected-(U4-T3OUT-Pad11)") (class "Default")
      (node (ref "U4") (pin "11") (pinfunction "T3OUT_11") (pintype "passive"))
    )
  )
)
